# untitled.net
KiCad netlist of a schematic drawn in EAGLE
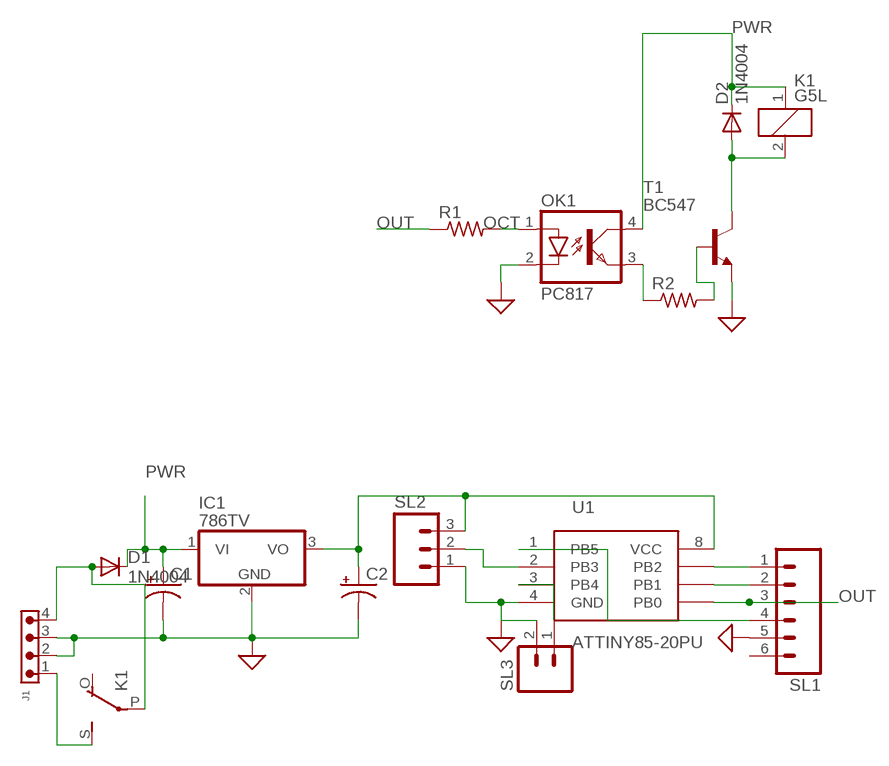
[diagram p0: schematic, sheet 1]

(export (version "E")
  (design (tool "Eeschema 10.0.6"))
  (components
    (comp (ref "C1")
      (value "CAPACITOR-PE5-10.5")
      (footprint "eagle-import:E5-10,5")
      (libsource (lib "eagle-import") (part "CAPACITOR-PE5-10.5"))
    )
    (comp (ref "C2")
      (value "CAPACITOR-PE2.5-5")
      (footprint "eagle-import:E2,5-5")
      (libsource (lib "eagle-import") (part "CAPACITOR-PE2.5-5"))
    )
    (comp (ref "D1")
      (value "1N4004")
      (footprint "eagle-import:DO41-10")
      (libsource (lib "eagle-import") (part "1N4004"))
    )
    (comp (ref "D2")
      (value "1N4004")
      (footprint "eagle-import:DO41-10")
      (libsource (lib "eagle-import") (part "1N4004"))
    )
    (comp (ref "IC1")
      (value "786TV")
      (footprint "eagle-import:TO220V")
      (libsource (lib "eagle-import") (part "78TV6"))
    )
    (comp (ref "J1")
      (value "691305530004")
      (footprint "eagle-import:691305530004")
      (libsource (lib "eagle-import") (part "691305530004"))
    )
    (comp (ref "K1")
      (value "G5L")
      (footprint "eagle-import:G5LE")
      (libsource (lib "eagle-import") (part "G5L"))
    )
    (comp (ref "OK1")
      (value "PC817")
      (footprint "eagle-import:DIL04")
      (fields (field (name "MPN") "PC817X4J000F"))
      (libsource (lib "eagle-import") (part "PC817"))
    )
    (comp (ref "R1")
      (value "R-US_0411/15")
      (footprint "eagle-import:0411_15")
      (libsource (lib "eagle-import") (part "R-US_0411/15"))
    )
    (comp (ref "R2")
      (value "R-US_0207/10")
      (footprint "eagle-import:0207_10")
      (libsource (lib "eagle-import") (part "adafruit_420_R-US_0207/10"))
    )
    (comp (ref "SL1")
      (value "M06")
      (footprint "eagle-import:06P")
      (libsource (lib "eagle-import") (part "M06"))
    )
    (comp (ref "SL2")
      (value "M03")
      (footprint "eagle-import:03P")
      (libsource (lib "eagle-import") (part "M03"))
    )
    (comp (ref "SL3")
      (value "M02")
      (footprint "eagle-import:02P")
      (libsource (lib "eagle-import") (part "M02"))
    )
    (comp (ref "T1")
      (value "BC547")
      (footprint "eagle-import:TO92")
      (libsource (lib "eagle-import") (part "BC547"))
    )
    (comp (ref "U1")
      (value "ATTINY85-20PU")
      (footprint "eagle-import:PDIP-8")
      (fields
        (field (name "DIGI_KEY_PART_NUMBER") "ATTINY85-20PU-ND")
        (field (name "MANUFACTURER") "Microchip Technology")
        (field (name "CREATED_BY") "PCBLayout.com")
      )
      (libsource (lib "eagle-import") (part "ATTINY85-20PU"))
    )
  )
  (nets
    (net (code "1") (name "/OCT") (class "Default")
      (node (ref "OK1") (pin "1") (pinfunction "A_1") (pintype "passive"))
      (node (ref "R1") (pin "2") (pinfunction "2_2") (pintype "passive"))
    )
    (net (code "2") (name "/OUT") (class "Default")
      (node (ref "R1") (pin "1") (pinfunction "1_1") (pintype "passive"))
      (node (ref "SL1") (pin "3") (pinfunction "3_3") (pintype "passive"))
      (node (ref "U1") (pin "5") (pinfunction "PB0_5") (pintype "bidirectional"))
    )
    (net (code "3") (name "/PWR") (class "Default")
      (node (ref "C1") (pin "+") (pinfunction "+_+") (pintype "passive"))
      (node (ref "D1") (pin "C") (pinfunction "C_C") (pintype "passive"))
      (node (ref "D2") (pin "C") (pinfunction "C_C") (pintype "passive"))
      (node (ref "IC1") (pin "1") (pinfunction "VI_1") (pintype "input"))
      (node (ref "K1") (pin "1") (pinfunction "1_1") (pintype "passive"))
      (node (ref "OK1") (pin "4") (pinfunction "COL_4") (pintype "passive"))
    )
    (net (code "4") (name "Net-(D1-PadA)") (class "Default")
      (node (ref "D1") (pin "A") (pinfunction "A_A") (pintype "passive"))
      (node (ref "J1") (pin "4") (pinfunction "4_4") (pintype "passive"))
      (node (ref "K1") (pin "P") (pinfunction "P_P") (pintype "passive"))
    )
    (net (code "5") (name "Net-(IC1-VO)") (class "Default")
      (node (ref "C2") (pin "+") (pinfunction "+_+") (pintype "passive"))
      (node (ref "IC1") (pin "3") (pinfunction "VO_3") (pintype "passive"))
      (node (ref "SL2") (pin "3") (pinfunction "3_3") (pintype "passive"))
      (node (ref "U1") (pin "8") (pinfunction "VCC_8") (pintype "power_in"))
    )
    (net (code "6") (name "Net-(J1-Pad1)") (class "Default")
      (node (ref "J1") (pin "1") (pinfunction "1_1") (pintype "passive"))
      (node (ref "K1") (pin "S") (pinfunction "S_S") (pintype "passive"))
    )
    (net (code "7") (name "Net-(OK1-EMIT)") (class "Default")
      (node (ref "OK1") (pin "3") (pinfunction "EMIT_3") (pintype "passive"))
      (node (ref "R2") (pin "1") (pinfunction "1_1") (pintype "passive"))
    )
    (net (code "8") (name "Net-(T1-B)") (class "Default")
      (node (ref "R2") (pin "2") (pinfunction "2_2") (pintype "passive"))
      (node (ref "T1") (pin "2") (pinfunction "B_2") (pintype "passive"))
    )
    (net (code "9") (name "Net-(T1-C)") (class "Default")
      (node (ref "D2") (pin "A") (pinfunction "A_A") (pintype "passive"))
      (node (ref "K1") (pin "2") (pinfunction "2_2") (pintype "passive"))
      (node (ref "T1") (pin "3") (pinfunction "C_3") (pintype "passive"))
    )
    (net (code "10") (name "Net-(U1-PB1)") (class "Default")
      (node (ref "SL1") (pin "2") (pinfunction "2_2") (pintype "passive"))
      (node (ref "U1") (pin "6") (pinfunction "PB1_6") (pintype "bidirectional"))
    )
    (net (code "11") (name "Net-(U1-PB2)") (class "Default")
      (node (ref "SL1") (pin "1") (pinfunction "1_1") (pintype "passive"))
      (node (ref "U1") (pin "7") (pinfunction "PB2_7") (pintype "bidirectional"))
    )
    (net (code "12") (name "Net-(U1-PB3)") (class "Default")
      (node (ref "SL2") (pin "2") (pinfunction "2_2") (pintype "passive"))
      (node (ref "U1") (pin "2") (pinfunction "PB3_2") (pintype "bidirectional"))
    )
    (net (code "13") (name "Net-(U1-PB4)") (class "Default")
      (node (ref "SL3") (pin "1") (pinfunction "1_1") (pintype "passive"))
      (node (ref "U1") (pin "3") (pinfunction "PB4_3") (pintype "bidirectional"))
    )
    (net (code "14") (name "Net-(U1-PB5)") (class "Default")
      (node (ref "SL1") (pin "4") (pinfunction "4_4") (pintype "passive"))
      (node (ref "U1") (pin "1") (pinfunction "PB5_1") (pintype "bidirectional"))
    )
    (net (code "15") (name "SUP") (class "Default")
      (node (ref "C1") (pin "-") (pinfunction "-_-") (pintype "passive"))
      (node (ref "C2") (pin "-") (pinfunction "-_-") (pintype "passive"))
      (node (ref "IC1") (pin "2") (pinfunction "GND_2") (pintype "passive"))
      (node (ref "J1") (pin "2") (pinfunction "2_2") (pintype "passive"))
      (node (ref "J1") (pin "3") (pinfunction "3_3") (pintype "passive"))
      (node (ref "OK1") (pin "2") (pinfunction "C_2") (pintype "passive"))
      (node (ref "SL1") (pin "5") (pinfunction "5_5") (pintype "passive"))
      (node (ref "SL2") (pin "1") (pinfunction "1_1") (pintype "passive"))
      (node (ref "SL3") (pin "2") (pinfunction "2_2") (pintype "passive"))
      (node (ref "T1") (pin "1") (pinfunction "E_1") (pintype "passive"))
      (node (ref "U1") (pin "4") (pinfunction "GND_4") (pintype "power_in"))
    )
    (net (code "16") (name "unconnected-(K1-PadO)") (class "Default")
      (node (ref "K1") (pin "O") (pinfunction "O_O") (pintype "passive"))
    )
    (net (code "17") (name "unconnected-(SL1-Pad6)") (class "Default")
      (node (ref "SL1") (pin "6") (pinfunction "6_6") (pintype "passive"))
    )
  )
)
